# pca10112_sheet8_FEM.net
KiCad netlist of a schematic drawn in Altium Designer
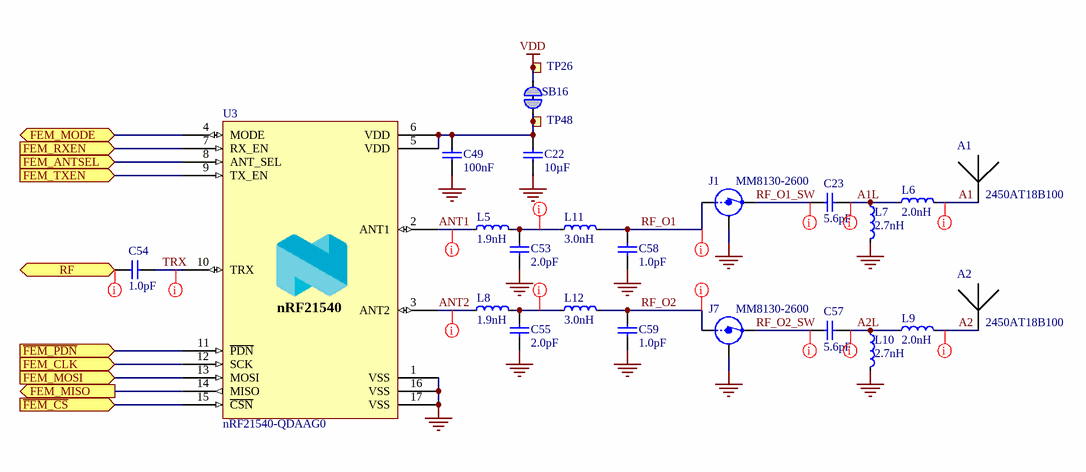
[diagram p0: pca10112_sheet8_FEM.SchDoc]

(export (version "E")
  (design (tool "Eeschema 10.0.6"))
  (components
    (comp (ref "A1")
      (value "2450AT18B100")
      (footprint "2450AT18B100")
      (description "2.45 GHz chip antenna")
      (fields
        (field (name "PART NUMBER") "Johanson 2450AT18B100")
        (field (name "MANUFACTURER") "Johanson Technology")
        (field (name "PUBLISHER") "Nordic Semiconductor")
        (field (name "AUTHOR") "rsk")
      )
      (libsource (lib "AltiumLib") (part "Antenna"))
    )
    (comp (ref "A2")
      (value "2450AT18B100")
      (footprint "2450AT18B100")
      (description "2.45 GHz chip antenna")
      (fields
        (field (name "PART NUMBER") "Johanson 2450AT18B100")
        (field (name "MANUFACTURER") "Johanson Technology")
        (field (name "PUBLISHER") "Nordic Semiconductor")
        (field (name "AUTHOR") "rsk")
      )
      (libsource (lib "AltiumLib") (part "Antenna"))
    )
    (comp (ref "C22")
      (value "10µF")
      (footprint "CAPC1608X06L")
      (description "Capacitor, X5R, ±20%")
      (fields
        (field (name "PART NUMBER") "C0603-10µ")
        (field (name "MANUFACTURER") "N.A.")
        (field (name "PUBLISHER") "Nordic Semiconductor")
        (field (name "AUTHOR") "rsk")
      )
      (libsource (lib "AltiumLib") (part "CAP"))
    )
    (comp (ref "C23")
      (value "5.6pF")
      (footprint "CAPC0603X03L_C")
      (description "Chip Cap 0201")
      (fields
        (field (name "PART NUMBER") "C0201-5.6p")
        (field (name "MANUFACTURER") "N.A.")
        (field (name "PUBLISHER") "Nordic Semiconductor")
        (field (name "AUTHOR") "rsk")
      )
      (libsource (lib "AltiumLib") (part "CAP"))
    )
    (comp (ref "C49")
      (value "100nF")
      (footprint "CAPC0603X03L_C")
      (description "Capacitor, X5R, ±10%")
      (fields
        (field (name "PART NUMBER") "C0201-100n")
        (field (name "MANUFACTURER") "N.A.")
        (field (name "PUBLISHER") "Nordic Semiconductor")
        (field (name "AUTHOR") "rsk")
      )
      (libsource (lib "AltiumLib") (part "CAP"))
    )
    (comp (ref "C53")
      (value "2.0pF")
      (footprint "CAPC0603X03L_C")
      (description "Capacitor, NP0, ±0.05pF, 25V")
      (fields
        (field (name "PART NUMBER") "C0201-2.0p-HQ-Murata")
        (field (name "MANUFACTURER") "Murata")
        (field (name "AUTHOR") "rsk")
      )
      (libsource (lib "AltiumLib") (part "CAP"))
    )
    (comp (ref "C54")
      (value "1.0pF")
      (footprint "CAPC0603X03L_C")
      (description "CAP CER 1PF 25V C0G/NP0 0201")
      (fields
        (field (name "PART NUMBER") "C0201-1p0")
        (field (name "MANUFACTURER") "Murata")
        (field (name "PUBLISHER") "Nordic Semiconductor")
        (field (name "AUTHOR") "rsk")
      )
      (libsource (lib "AltiumLib") (part "CAP"))
    )
    (comp (ref "C55")
      (value "2.0pF")
      (footprint "CAPC0603X03L_C")
      (description "Capacitor, NP0, ±0.05pF, 25V")
      (fields
        (field (name "PART NUMBER") "C0201-2.0p-HQ-Murata")
        (field (name "MANUFACTURER") "Murata")
        (field (name "AUTHOR") "rsk")
      )
      (libsource (lib "AltiumLib") (part "CAP"))
    )
    (comp (ref "C57")
      (value "5.6pF")
      (footprint "CAPC0603X03L_C")
      (description "Chip Cap 0201")
      (fields
        (field (name "PART NUMBER") "C0201-5.6p")
        (field (name "MANUFACTURER") "N.A.")
        (field (name "PUBLISHER") "Nordic Semiconductor")
        (field (name "AUTHOR") "rsk")
      )
      (libsource (lib "AltiumLib") (part "CAP"))
    )
    (comp (ref "C58")
      (value "1.0pF")
      (footprint "CAPC0603X03L_C")
      (description "RF Chip Cap 0201")
      (fields
        (field (name "PART NUMBER") "C0201-1.0p_RF")
        (field (name "MANUFACTURER") "N.A.")
        (field (name "AUTHOR") "rsk")
      )
      (libsource (lib "AltiumLib") (part "CAP"))
    )
    (comp (ref "C59")
      (value "1.0pF")
      (footprint "CAPC0603X03L_C")
      (description "RF Chip Cap 0201")
      (fields
        (field (name "PART NUMBER") "C0201-1.0p_RF")
        (field (name "MANUFACTURER") "N.A.")
        (field (name "AUTHOR") "rsk")
      )
      (libsource (lib "AltiumLib") (part "CAP"))
    )
    (comp (ref "J1")
      (value "MM8130-2600")
      (footprint "COAXIAL-SWF")
      (description "Coaxial Connector with Switch")
      (fields
        (field (name "MANUFACTURER") "Murata")
        (field (name "PUBLISHER") "Nordic Semiconductor")
        (field (name "AUTHOR") "rsk")
      )
      (libsource (lib "AltiumLib") (part "Coaxial-Internal-SW"))
    )
    (comp (ref "J7")
      (value "MM8130-2600")
      (footprint "COAXIAL-SWF")
      (description "Coaxial Connector with Switch")
      (fields
        (field (name "MANUFACTURER") "Murata")
        (field (name "PUBLISHER") "Nordic Semiconductor")
        (field (name "AUTHOR") "rsk")
      )
      (libsource (lib "AltiumLib") (part "Coaxial-Internal-SW"))
    )
    (comp (ref "L5")
      (value "1.9nH")
      (footprint "INDC0603X03L_C")
      (description "Inductor, 600mA, ±0.1ｎH, 120mOhm")
      (fields
        (field (name "PART NUMBER") "L0201-1n9-HQ-Murata")
        (field (name "MANUFACTURER") "Murata")
        (field (name "PUBLISHER") "Nordic Semiconductor")
        (field (name "AUTHOR") "rsk")
      )
      (libsource (lib "AltiumLib") (part "IND"))
    )
    (comp (ref "L6")
      (value "2.0nH")
      (footprint "INDC0603X03L_C")
      (description "Inductor, 600mA, ±0.1ｎH, 120mOhm")
      (fields
        (field (name "PART NUMBER") "L0201-2n0-HQ-Murata")
        (field (name "MANUFACTURER") "Murata")
        (field (name "PUBLISHER") "Nordic Semiconductor")
        (field (name "AUTHOR") "rsk")
      )
      (libsource (lib "AltiumLib") (part "IND"))
    )
    (comp (ref "L7")
      (value "2.7nH")
      (footprint "INDC0603X03L_C")
      (description "Inductor, 600mA, ±0.1ｎH, 120mOhm")
      (fields
        (field (name "PART NUMBER") "L0201-2n7-HQ-Murata")
        (field (name "MANUFACTURER") "Murata")
        (field (name "PUBLISHER") "Nordic Semiconductor")
        (field (name "AUTHOR") "rsk")
      )
      (libsource (lib "AltiumLib") (part "IND"))
    )
    (comp (ref "L8")
      (value "1.9nH")
      (footprint "INDC0603X03L_C")
      (description "Inductor, 600mA, ±0.1ｎH, 120mOhm")
      (fields
        (field (name "PART NUMBER") "L0201-1n9-HQ-Murata")
        (field (name "MANUFACTURER") "Murata")
        (field (name "PUBLISHER") "Nordic Semiconductor")
        (field (name "AUTHOR") "rsk")
      )
      (libsource (lib "AltiumLib") (part "IND"))
    )
    (comp (ref "L9")
      (value "2.0nH")
      (footprint "INDC0603X03L_C")
      (description "Inductor, 600mA, ±0.1ｎH, 120mOhm")
      (fields
        (field (name "PART NUMBER") "L0201-2n0-HQ-Murata")
        (field (name "MANUFACTURER") "Murata")
        (field (name "PUBLISHER") "Nordic Semiconductor")
        (field (name "AUTHOR") "rsk")
      )
      (libsource (lib "AltiumLib") (part "IND"))
    )
    (comp (ref "L10")
      (value "2.7nH")
      (footprint "INDC0603X03L_C")
      (description "Inductor, 600mA, ±0.1ｎH, 120mOhm")
      (fields
        (field (name "PART NUMBER") "L0201-2n7-HQ-Murata")
        (field (name "MANUFACTURER") "Murata")
        (field (name "PUBLISHER") "Nordic Semiconductor")
        (field (name "AUTHOR") "rsk")
      )
      (libsource (lib "AltiumLib") (part "IND"))
    )
    (comp (ref "L11")
      (value "3.0nH")
      (footprint "INDC0603X03L_C")
      (description "Inductor, 600mA, ±0.1ｎH, 120mOhm")
      (fields
        (field (name "PART NUMBER") "L0201-3n0-HQ-Murata")
        (field (name "MANUFACTURER") "Murata")
        (field (name "AUTHOR") "rsk")
      )
      (libsource (lib "AltiumLib") (part "IND"))
    )
    (comp (ref "L12")
      (value "3.0nH")
      (footprint "INDC0603X03L_C")
      (description "Inductor, 600mA, ±0.1ｎH, 120mOhm")
      (fields
        (field (name "PART NUMBER") "L0201-3n0-HQ-Murata")
        (field (name "MANUFACTURER") "Murata")
        (field (name "AUTHOR") "rsk")
      )
      (libsource (lib "AltiumLib") (part "IND"))
    )
    (comp (ref "SB16")
      (value "Solderbridge")
      (footprint "Solderbridge_Shorted")
      (description "Shorted Solderbridge")
      (fields
        (field (name "PART NUMBER") "Solderbridge Shorted")
        (field (name "MANUFACTURER") "N.A.")
        (field (name "PUBLISHER") "Nordic Semiconductor")
        (field (name "AUTHOR") "rsk")
      )
      (libsource (lib "AltiumLib") (part "SOLDERBRIDGE_SHORTED"))
    )
    (comp (ref "TP26")
      (value "Ø1.0mm,SMD")
      (footprint "TP_SMD_Ø1.0mm")
      (description "1.0mm circular SMD testpad")
      (fields
        (field (name "PART NUMBER") "TP_SMD_Ø1.0MM")
        (field (name "MANUFACTURER") "Nordic Semiconductor")
        (field (name "PUBLISHER") "Nordic Semiconductor")
        (field (name "AUTHOR") "rsk")
      )
      (libsource (lib "AltiumLib") (part "TESTPAD"))
    )
    (comp (ref "TP48")
      (value "Ø1.0mm,SMD")
      (footprint "TP_SMD_Ø1.0mm")
      (description "1.0mm circular SMD testpad")
      (fields
        (field (name "PART NUMBER") "TP_SMD_Ø1.0MM")
        (field (name "MANUFACTURER") "Nordic Semiconductor")
        (field (name "PUBLISHER") "Nordic Semiconductor")
        (field (name "AUTHOR") "rsk")
      )
      (libsource (lib "AltiumLib") (part "TESTPAD"))
    )
    (comp (ref "U3")
      (value "nRF21540-QDAAG0")
      (footprint "QFN65P400X400X65_HS-17N")
      (description "Radio front-end / range extender for 2.4GHz")
      (fields (field (name "MANUFACTURER") "Nordic Semiconductor") (field (name "AUTHOR") "hany"))
      (libsource (lib "AltiumLib") (part "nRF21540-QDAA"))
    )
  )
  (nets
    (net (code "1") (name "/A1") (class "Default")
      (node (ref "A1") (pin "1") (pinfunction "1_1") (pintype "passive"))
      (node (ref "L6") (pin "2") (pinfunction "2_2") (pintype "passive"))
    )
    (net (code "2") (name "/A1L") (class "Default")
      (node (ref "C23") (pin "1") (pinfunction "1_1") (pintype "passive"))
      (node (ref "L6") (pin "1") (pinfunction "1_1") (pintype "passive"))
      (node (ref "L7") (pin "1") (pinfunction "1_1") (pintype "passive"))
    )
    (net (code "3") (name "/A2") (class "Default")
      (node (ref "A2") (pin "1") (pinfunction "1_1") (pintype "passive"))
      (node (ref "L9") (pin "2") (pinfunction "2_2") (pintype "passive"))
    )
    (net (code "4") (name "/A2L") (class "Default")
      (node (ref "C57") (pin "1") (pinfunction "1_1") (pintype "passive"))
      (node (ref "L10") (pin "1") (pinfunction "1_1") (pintype "passive"))
      (node (ref "L9") (pin "1") (pinfunction "1_1") (pintype "passive"))
    )
    (net (code "5") (name "/ANT1") (class "Default")
      (node (ref "L5") (pin "1") (pinfunction "1_1") (pintype "passive"))
      (node (ref "U3") (pin "2") (pinfunction "ANT1_2") (pintype "bidirectional"))
    )
    (net (code "6") (name "/ANT2") (class "Default")
      (node (ref "L8") (pin "1") (pinfunction "1_1") (pintype "passive"))
      (node (ref "U3") (pin "3") (pinfunction "ANT2_3") (pintype "bidirectional"))
    )
    (net (code "7") (name "/FEM_ANTSEL") (class "Default")
      (node (ref "U3") (pin "8") (pinfunction "ANT_SEL_8") (pintype "input"))
    )
    (net (code "8") (name "/FEM_CLK") (class "Default")
      (node (ref "U3") (pin "12") (pinfunction "SCK_12") (pintype "input"))
    )
    (net (code "9") (name "/FEM_MISO") (class "Default")
      (node (ref "U3") (pin "14") (pinfunction "MISO_14") (pintype "output"))
    )
    (net (code "10") (name "/FEM_MODE") (class "Default")
      (node (ref "U3") (pin "4") (pinfunction "MODE_4") (pintype "bidirectional"))
    )
    (net (code "11") (name "/FEM_MOSI") (class "Default")
      (node (ref "U3") (pin "13") (pinfunction "MOSI_13") (pintype "input"))
    )
    (net (code "12") (name "/FEM_RXEN") (class "Default")
      (node (ref "U3") (pin "7") (pinfunction "RX_EN_7") (pintype "input"))
    )
    (net (code "13") (name "/FEM_TXEN") (class "Default")
      (node (ref "U3") (pin "9") (pinfunction "TX_EN_9") (pintype "input"))
    )
    (net (code "14") (name "/RF") (class "Default")
      (node (ref "C54") (pin "1") (pinfunction "1_1") (pintype "passive"))
    )
    (net (code "15") (name "/RF_O1") (class "Default")
      (node (ref "C58") (pin "2") (pinfunction "2_2") (pintype "passive"))
      (node (ref "J1") (pin "1") (pinfunction "IN_1") (pintype "passive"))
      (node (ref "L11") (pin "2") (pinfunction "2_2") (pintype "passive"))
    )
    (net (code "16") (name "/RF_O1_SW") (class "Default")
      (node (ref "C23") (pin "2") (pinfunction "2_2") (pintype "passive"))
      (node (ref "J1") (pin "3") (pinfunction "OUT_3") (pintype "passive"))
    )
    (net (code "17") (name "/RF_O2") (class "Default")
      (node (ref "C59") (pin "2") (pinfunction "2_2") (pintype "passive"))
      (node (ref "J7") (pin "1") (pinfunction "IN_1") (pintype "passive"))
      (node (ref "L12") (pin "2") (pinfunction "2_2") (pintype "passive"))
    )
    (net (code "18") (name "/RF_O2_SW") (class "Default")
      (node (ref "C57") (pin "2") (pinfunction "2_2") (pintype "passive"))
      (node (ref "J7") (pin "3") (pinfunction "OUT_3") (pintype "passive"))
    )
    (net (code "19") (name "/TRX") (class "Default")
      (node (ref "C54") (pin "2") (pinfunction "2_2") (pintype "passive"))
      (node (ref "U3") (pin "10") (pinfunction "TRX_10") (pintype "bidirectional"))
    )
    (net (code "20") (name "/~{FEM_CS}") (class "Default")
      (node (ref "U3") (pin "15") (pinfunction "~{CSN}_15") (pintype "input"))
    )
    (net (code "21") (name "/~{FEM_PDN}") (class "Default")
      (node (ref "U3") (pin "11") (pinfunction "~{PDN}_11") (pintype "input"))
    )
    (net (code "22") (name "GND") (class "Default")
      (node (ref "C22") (pin "1") (pinfunction "1_1") (pintype "passive"))
      (node (ref "C49") (pin "1") (pinfunction "1_1") (pintype "passive"))
      (node (ref "C53") (pin "1") (pinfunction "1_1") (pintype "passive"))
      (node (ref "C55") (pin "1") (pinfunction "1_1") (pintype "passive"))
      (node (ref "C58") (pin "1") (pinfunction "1_1") (pintype "passive"))
      (node (ref "C59") (pin "1") (pinfunction "1_1") (pintype "passive"))
      (node (ref "J1") (pin "2") (pinfunction "Shield_2") (pintype "passive"))
      (node (ref "J7") (pin "2") (pinfunction "Shield_2") (pintype "passive"))
      (node (ref "L10") (pin "2") (pinfunction "2_2") (pintype "passive"))
      (node (ref "L7") (pin "2") (pinfunction "2_2") (pintype "passive"))
      (node (ref "U3") (pin "1") (pinfunction "VSS_1") (pintype "power_in"))
      (node (ref "U3") (pin "16") (pinfunction "VSS_16") (pintype "power_in"))
      (node (ref "U3") (pin "17") (pinfunction "VSS_17") (pintype "power_in"))
    )
    (net (code "23") (name "Net-(C53-Pad2)") (class "Default")
      (node (ref "C53") (pin "2") (pinfunction "2_2") (pintype "passive"))
      (node (ref "L11") (pin "1") (pinfunction "1_1") (pintype "passive"))
      (node (ref "L5") (pin "2") (pinfunction "2_2") (pintype "passive"))
    )
    (net (code "24") (name "Net-(C55-Pad2)") (class "Default")
      (node (ref "C55") (pin "2") (pinfunction "2_2") (pintype "passive"))
      (node (ref "L12") (pin "1") (pinfunction "1_1") (pintype "passive"))
      (node (ref "L8") (pin "2") (pinfunction "2_2") (pintype "passive"))
    )
    (net (code "25") (name "Net-(SB16-1)") (class "Default")
      (node (ref "C22") (pin "2") (pinfunction "2_2") (pintype "passive"))
      (node (ref "C49") (pin "2") (pinfunction "2_2") (pintype "passive"))
      (node (ref "SB16") (pin "2") (pinfunction "1_2") (pintype "passive"))
      (node (ref "TP48") (pin "1") (pinfunction "1_1") (pintype "passive"))
      (node (ref "U3") (pin "5") (pinfunction "VDD_5") (pintype "power_in"))
      (node (ref "U3") (pin "6") (pinfunction "VDD_6") (pintype "power_in"))
    )
    (net (code "26") (name "VDD") (class "Default")
      (node (ref "SB16") (pin "1") (pinfunction "0_1") (pintype "passive"))
      (node (ref "TP26") (pin "1") (pinfunction "1_1") (pintype "passive"))
    )
  )
)
